# SCH_pcie_2022-12-23.net
KiCad netlist of a schematic drawn in EasyEDA
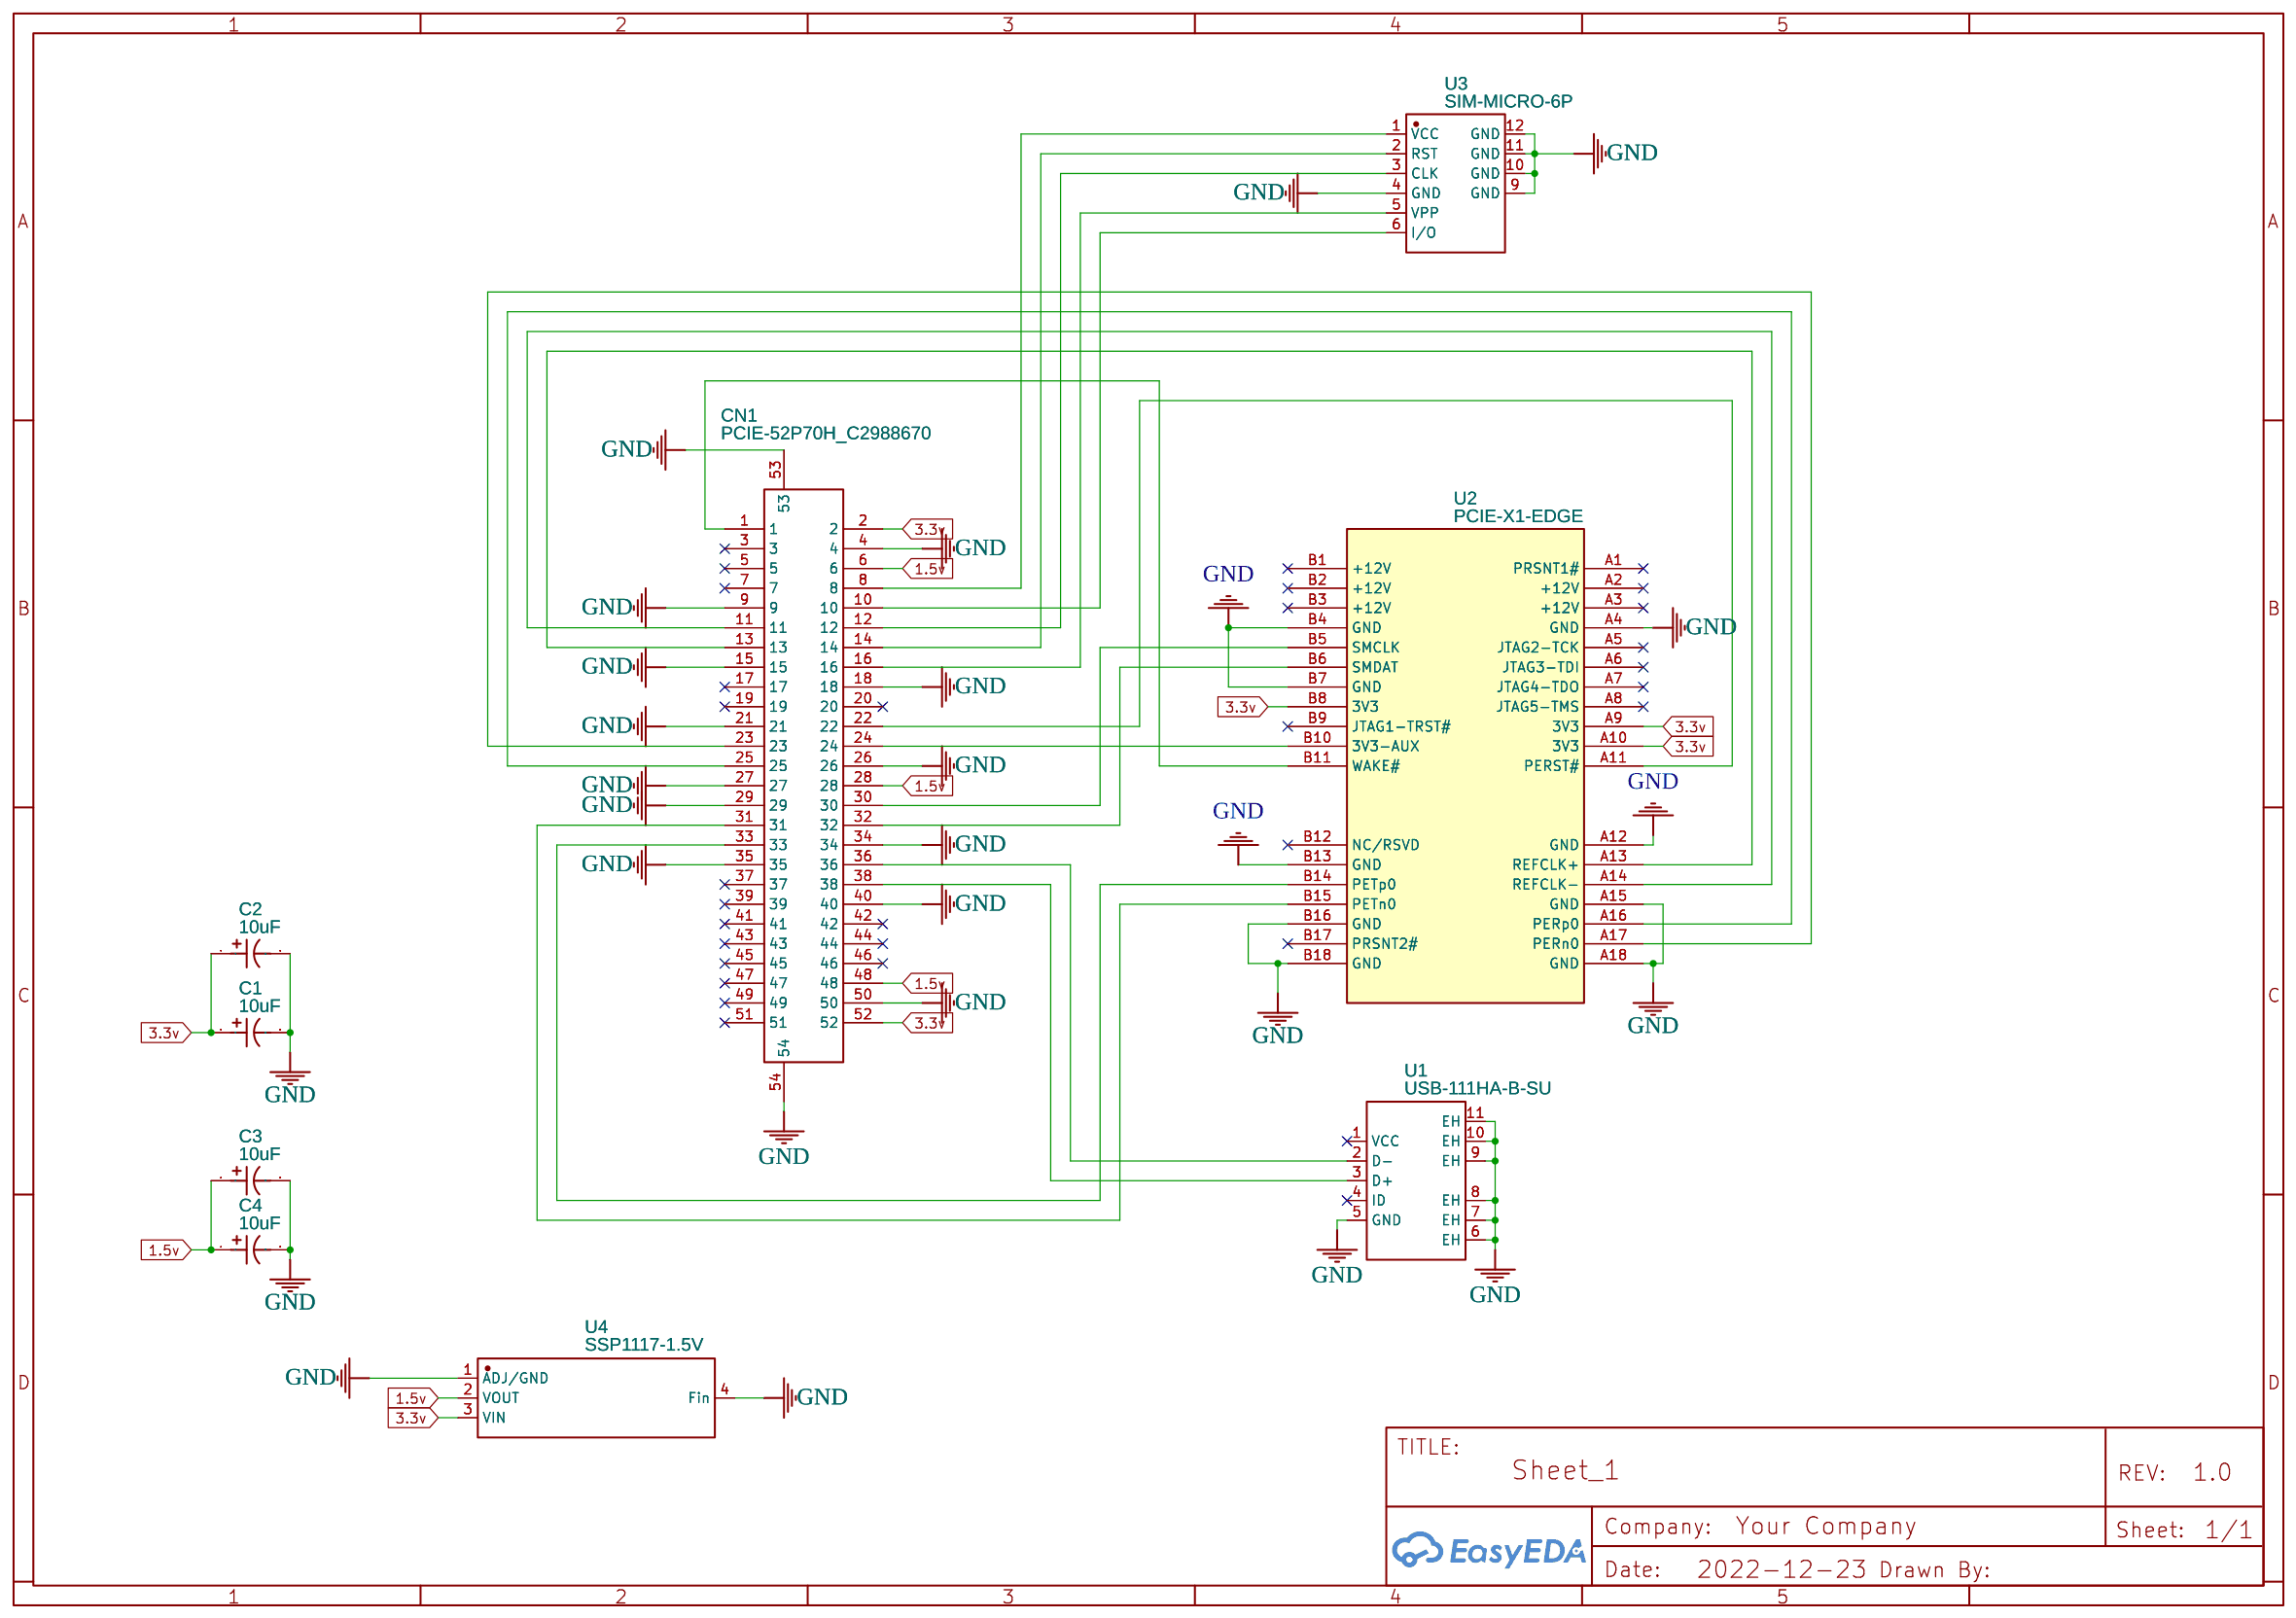
[diagram p0: schematic sheet]

(export (version "E")
  (design (tool "Eeschema 10.0.6"))
  (components
    (comp (ref "C1")
      (value "10uF")
      (fields
        (field (name "BOM_Manufacturer Part") "XT10UF35V90RV0070")
        (field (name "BOM_Supplier Part") "C2992602")
      )
      (libsource (lib "") (part "XT10UF35V90RV0070_1"))
    )
    (comp (ref "C2")
      (value "10uF")
      (fields
        (field (name "BOM_Manufacturer Part") "XT10UF35V90RV0070")
        (field (name "BOM_Supplier Part") "C2992602")
      )
      (libsource (lib "") (part "XT10UF35V90RV0070_1"))
    )
    (comp (ref "C3")
      (value "10uF")
      (fields
        (field (name "BOM_Manufacturer Part") "XT10UF35V90RV0070")
        (field (name "BOM_Supplier Part") "C2992602")
      )
      (libsource (lib "") (part "XT10UF35V90RV0070"))
    )
    (comp (ref "C4")
      (value "10uF")
      (fields
        (field (name "BOM_Manufacturer Part") "XT10UF35V90RV0070")
        (field (name "BOM_Supplier Part") "C2992602")
      )
      (libsource (lib "") (part "XT10UF35V90RV0070"))
    )
    (comp (ref "CN1")
      (value "PCIE-52P70H_C2988670")
      (fields
        (field (name "BOM_Manufacturer Part") "PCIE-52P70H")
        (field (name "BOM_Supplier Part") "C2988670")
      )
      (libsource (lib "") (part "PCIE-52P70H_C2988670"))
    )
    (comp (ref "U1")
      (value "USB-111HA-B-SU")
      (fields (field (name "BOM_Supplier Part") "C2939565"))
      (libsource (lib "") (part "USB-111HA-B-SU"))
    )
    (comp (ref "U2") (value "PCIE-X1-EDGE") (libsource (lib "") (part "PCIE-X1-EDGE")))
    (comp (ref "U3")
      (value "SIM-MICRO-6P")
      (fields (field (name "BOM_Supplier Part") "C9900009166"))
      (libsource (lib "") (part "SIM-MICRO-6P"))
    )
    (comp (ref "U4")
      (value "SSP1117-1.5V")
      (fields (field (name "BOM_Supplier Part") "C308941"))
      (libsource (lib "") (part "SSP1117-1.5V"))
    )
  )
  (nets
    (net (code "1") (name "1.5v") (class "Default")
      (node (ref "C3") (pin "1") (pinfunction "1_1") (pintype "input"))
      (node (ref "C4") (pin "1") (pinfunction "1_1") (pintype "input"))
      (node (ref "CN1") (pin "28") (pinfunction "28_28") (pintype "unspecified"))
      (node (ref "CN1") (pin "48") (pinfunction "48_48") (pintype "unspecified"))
      (node (ref "CN1") (pin "6") (pinfunction "6_6") (pintype "unspecified"))
      (node (ref "U4") (pin "2") (pinfunction "VOUT_2") (pintype "unspecified"))
    )
    (net (code "2") (name "3.3v") (class "Default")
      (node (ref "C1") (pin "1") (pinfunction "1_1") (pintype "input"))
      (node (ref "C2") (pin "1") (pinfunction "1_1") (pintype "input"))
      (node (ref "CN1") (pin "2") (pinfunction "2_2") (pintype "unspecified"))
      (node (ref "CN1") (pin "52") (pinfunction "52_52") (pintype "unspecified"))
      (node (ref "U2") (pin "A10") (pinfunction "3V3_A10") (pintype "unspecified"))
      (node (ref "U2") (pin "A9") (pinfunction "3V3_A9") (pintype "unspecified"))
      (node (ref "U2") (pin "B8") (pinfunction "3V3_B8") (pintype "unspecified"))
      (node (ref "U4") (pin "3") (pinfunction "VIN_3") (pintype "unspecified"))
    )
    (net (code "3") (name "GND") (class "Default")
      (node (ref "C1") (pin "2") (pinfunction "2_2") (pintype "input"))
      (node (ref "C2") (pin "2") (pinfunction "2_2") (pintype "input"))
      (node (ref "C3") (pin "2") (pinfunction "2_2") (pintype "input"))
      (node (ref "C4") (pin "2") (pinfunction "2_2") (pintype "input"))
      (node (ref "CN1") (pin "15") (pinfunction "15_15") (pintype "unspecified"))
      (node (ref "CN1") (pin "18") (pinfunction "18_18") (pintype "unspecified"))
      (node (ref "CN1") (pin "21") (pinfunction "21_21") (pintype "unspecified"))
      (node (ref "CN1") (pin "26") (pinfunction "26_26") (pintype "unspecified"))
      (node (ref "CN1") (pin "27") (pinfunction "27_27") (pintype "unspecified"))
      (node (ref "CN1") (pin "29") (pinfunction "29_29") (pintype "unspecified"))
      (node (ref "CN1") (pin "34") (pinfunction "34_34") (pintype "unspecified"))
      (node (ref "CN1") (pin "35") (pinfunction "35_35") (pintype "unspecified"))
      (node (ref "CN1") (pin "4") (pinfunction "4_4") (pintype "unspecified"))
      (node (ref "CN1") (pin "40") (pinfunction "40_40") (pintype "unspecified"))
      (node (ref "CN1") (pin "50") (pinfunction "50_50") (pintype "unspecified"))
      (node (ref "CN1") (pin "53") (pinfunction "53_53") (pintype "unspecified"))
      (node (ref "CN1") (pin "54") (pinfunction "54_54") (pintype "unspecified"))
      (node (ref "CN1") (pin "9") (pinfunction "9_9") (pintype "unspecified"))
      (node (ref "U1") (pin "10") (pinfunction "EH_10") (pintype "unspecified"))
      (node (ref "U1") (pin "11") (pinfunction "EH_11") (pintype "unspecified"))
      (node (ref "U1") (pin "5") (pinfunction "GND_5") (pintype "input"))
      (node (ref "U1") (pin "6") (pinfunction "EH_6") (pintype "unspecified"))
      (node (ref "U1") (pin "7") (pinfunction "EH_7") (pintype "unspecified"))
      (node (ref "U1") (pin "8") (pinfunction "EH_8") (pintype "unspecified"))
      (node (ref "U1") (pin "9") (pinfunction "EH_9") (pintype "unspecified"))
      (node (ref "U2") (pin "A12") (pinfunction "GND_A12") (pintype "unspecified"))
      (node (ref "U2") (pin "A15") (pinfunction "GND_A15") (pintype "unspecified"))
      (node (ref "U2") (pin "A18") (pinfunction "GND_A18") (pintype "unspecified"))
      (node (ref "U2") (pin "A4") (pinfunction "GND_A4") (pintype "unspecified"))
      (node (ref "U2") (pin "B13") (pinfunction "GND_B13") (pintype "unspecified"))
      (node (ref "U2") (pin "B16") (pinfunction "GND_B16") (pintype "unspecified"))
      (node (ref "U2") (pin "B18") (pinfunction "GND_B18") (pintype "unspecified"))
      (node (ref "U2") (pin "B4") (pinfunction "GND_B4") (pintype "unspecified"))
      (node (ref "U2") (pin "B7") (pinfunction "GND_B7") (pintype "unspecified"))
      (node (ref "U3") (pin "10") (pinfunction "GND_10") (pintype "unspecified"))
      (node (ref "U3") (pin "11") (pinfunction "GND_11") (pintype "unspecified"))
      (node (ref "U3") (pin "12") (pinfunction "GND_12") (pintype "unspecified"))
      (node (ref "U3") (pin "4") (pinfunction "GND_4") (pintype "unspecified"))
      (node (ref "U3") (pin "9") (pinfunction "GND_9") (pintype "unspecified"))
      (node (ref "U4") (pin "1") (pinfunction "ADJ/GND_1") (pintype "unspecified"))
      (node (ref "U4") (pin "4") (pinfunction "Fin_4") (pintype "unspecified"))
    )
    (net (code "4") (name "Net-(U1-D+)") (class "Default")
      (node (ref "CN1") (pin "38") (pinfunction "38_38") (pintype "unspecified"))
      (node (ref "U1") (pin "3") (pinfunction "D+_3") (pintype "input"))
    )
    (net (code "5") (name "Net-(U1-D-)") (class "Default")
      (node (ref "CN1") (pin "36") (pinfunction "36_36") (pintype "unspecified"))
      (node (ref "U1") (pin "2") (pinfunction "D-_2") (pintype "input"))
    )
    (net (code "6") (name "Net-(U2-3V3-AUX)") (class "Default")
      (node (ref "CN1") (pin "24") (pinfunction "24_24") (pintype "unspecified"))
      (node (ref "U2") (pin "B10") (pinfunction "3V3-AUX_B10") (pintype "unspecified"))
    )
    (net (code "7") (name "Net-(U2-PERST#)") (class "Default")
      (node (ref "CN1") (pin "22") (pinfunction "22_22") (pintype "unspecified"))
      (node (ref "U2") (pin "A11") (pinfunction "PERST#_A11") (pintype "unspecified"))
    )
    (net (code "8") (name "Net-(U2-PERn0)") (class "Default")
      (node (ref "CN1") (pin "23") (pinfunction "23_23") (pintype "unspecified"))
      (node (ref "U2") (pin "A17") (pinfunction "PERn0_A17") (pintype "unspecified"))
    )
    (net (code "9") (name "Net-(U2-PERp0)") (class "Default")
      (node (ref "CN1") (pin "25") (pinfunction "25_25") (pintype "unspecified"))
      (node (ref "U2") (pin "A16") (pinfunction "PERp0_A16") (pintype "unspecified"))
    )
    (net (code "10") (name "Net-(U2-PETn0)") (class "Default")
      (node (ref "CN1") (pin "31") (pinfunction "31_31") (pintype "unspecified"))
      (node (ref "U2") (pin "B15") (pinfunction "PETn0_B15") (pintype "unspecified"))
    )
    (net (code "11") (name "Net-(U2-PETp0)") (class "Default")
      (node (ref "CN1") (pin "33") (pinfunction "33_33") (pintype "unspecified"))
      (node (ref "U2") (pin "B14") (pinfunction "PETp0_B14") (pintype "unspecified"))
    )
    (net (code "12") (name "Net-(U2-REFCLK+)") (class "Default")
      (node (ref "CN1") (pin "13") (pinfunction "13_13") (pintype "unspecified"))
      (node (ref "U2") (pin "A13") (pinfunction "REFCLK+_A13") (pintype "unspecified"))
    )
    (net (code "13") (name "Net-(U2-REFCLK-)") (class "Default")
      (node (ref "CN1") (pin "11") (pinfunction "11_11") (pintype "unspecified"))
      (node (ref "U2") (pin "A14") (pinfunction "REFCLK-_A14") (pintype "unspecified"))
    )
    (net (code "14") (name "Net-(U2-SMCLK)") (class "Default")
      (node (ref "CN1") (pin "30") (pinfunction "30_30") (pintype "unspecified"))
      (node (ref "U2") (pin "B5") (pinfunction "SMCLK_B5") (pintype "unspecified"))
    )
    (net (code "15") (name "Net-(U2-SMDAT)") (class "Default")
      (node (ref "CN1") (pin "32") (pinfunction "32_32") (pintype "unspecified"))
      (node (ref "U2") (pin "B6") (pinfunction "SMDAT_B6") (pintype "unspecified"))
    )
    (net (code "16") (name "Net-(U2-WAKE#)") (class "Default")
      (node (ref "CN1") (pin "1") (pinfunction "1_1") (pintype "unspecified"))
      (node (ref "U2") (pin "B11") (pinfunction "WAKE#_B11") (pintype "unspecified"))
    )
    (net (code "17") (name "Net-(U3-CLK)") (class "Default")
      (node (ref "CN1") (pin "12") (pinfunction "12_12") (pintype "unspecified"))
      (node (ref "U3") (pin "3") (pinfunction "CLK_3") (pintype "unspecified"))
    )
    (net (code "18") (name "Net-(U3-I{slash}O)") (class "Default")
      (node (ref "CN1") (pin "10") (pinfunction "10_10") (pintype "unspecified"))
      (node (ref "U3") (pin "6") (pinfunction "I/O_6") (pintype "unspecified"))
    )
    (net (code "19") (name "Net-(U3-RST)") (class "Default")
      (node (ref "CN1") (pin "14") (pinfunction "14_14") (pintype "unspecified"))
      (node (ref "U3") (pin "2") (pinfunction "RST_2") (pintype "unspecified"))
    )
    (net (code "20") (name "Net-(U3-VCC)") (class "Default")
      (node (ref "CN1") (pin "8") (pinfunction "8_8") (pintype "unspecified"))
      (node (ref "U3") (pin "1") (pinfunction "VCC_1") (pintype "unspecified"))
    )
    (net (code "21") (name "Net-(U3-VPP)") (class "Default")
      (node (ref "CN1") (pin "16") (pinfunction "16_16") (pintype "unspecified"))
      (node (ref "U3") (pin "5") (pinfunction "VPP_5") (pintype "unspecified"))
    )
    (net (code "22") (name "unconnected-(CN1-Pad3)") (class "Default")
      (node (ref "CN1") (pin "3") (pinfunction "3_3") (pintype "unspecified+no_connect"))
    )
    (net (code "23") (name "unconnected-(CN1-Pad5)") (class "Default")
      (node (ref "CN1") (pin "5") (pinfunction "5_5") (pintype "unspecified+no_connect"))
    )
    (net (code "24") (name "unconnected-(CN1-Pad7)") (class "Default")
      (node (ref "CN1") (pin "7") (pinfunction "7_7") (pintype "unspecified+no_connect"))
    )
    (net (code "25") (name "unconnected-(CN1-Pad17)") (class "Default")
      (node (ref "CN1") (pin "17") (pinfunction "17_17") (pintype "unspecified+no_connect"))
    )
    (net (code "26") (name "unconnected-(CN1-Pad19)") (class "Default")
      (node (ref "CN1") (pin "19") (pinfunction "19_19") (pintype "unspecified+no_connect"))
    )
    (net (code "27") (name "unconnected-(CN1-Pad20)") (class "Default")
      (node (ref "CN1") (pin "20") (pinfunction "20_20") (pintype "unspecified+no_connect"))
    )
    (net (code "28") (name "unconnected-(CN1-Pad37)") (class "Default")
      (node (ref "CN1") (pin "37") (pinfunction "37_37") (pintype "unspecified+no_connect"))
    )
    (net (code "29") (name "unconnected-(CN1-Pad39)") (class "Default")
      (node (ref "CN1") (pin "39") (pinfunction "39_39") (pintype "unspecified+no_connect"))
    )
    (net (code "30") (name "unconnected-(CN1-Pad41)") (class "Default")
      (node (ref "CN1") (pin "41") (pinfunction "41_41") (pintype "unspecified+no_connect"))
    )
    (net (code "31") (name "unconnected-(CN1-Pad42)") (class "Default")
      (node (ref "CN1") (pin "42") (pinfunction "42_42") (pintype "unspecified+no_connect"))
    )
    (net (code "32") (name "unconnected-(CN1-Pad43)") (class "Default")
      (node (ref "CN1") (pin "43") (pinfunction "43_43") (pintype "unspecified+no_connect"))
    )
    (net (code "33") (name "unconnected-(CN1-Pad44)") (class "Default")
      (node (ref "CN1") (pin "44") (pinfunction "44_44") (pintype "unspecified+no_connect"))
    )
    (net (code "34") (name "unconnected-(CN1-Pad45)") (class "Default")
      (node (ref "CN1") (pin "45") (pinfunction "45_45") (pintype "unspecified+no_connect"))
    )
    (net (code "35") (name "unconnected-(CN1-Pad46)") (class "Default")
      (node (ref "CN1") (pin "46") (pinfunction "46_46") (pintype "unspecified+no_connect"))
    )
    (net (code "36") (name "unconnected-(CN1-Pad47)") (class "Default")
      (node (ref "CN1") (pin "47") (pinfunction "47_47") (pintype "unspecified+no_connect"))
    )
    (net (code "37") (name "unconnected-(CN1-Pad49)") (class "Default")
      (node (ref "CN1") (pin "49") (pinfunction "49_49") (pintype "unspecified+no_connect"))
    )
    (net (code "38") (name "unconnected-(CN1-Pad51)") (class "Default")
      (node (ref "CN1") (pin "51") (pinfunction "51_51") (pintype "unspecified+no_connect"))
    )
    (net (code "39") (name "unconnected-(U1-ID-Pad4)") (class "Default")
      (node (ref "U1") (pin "4") (pinfunction "ID_4") (pintype "input+no_connect"))
    )
    (net (code "40") (name "unconnected-(U1-VCC-Pad1)") (class "Default")
      (node (ref "U1") (pin "1") (pinfunction "VCC_1") (pintype "input+no_connect"))
    )
    (net (code "41") (name "unconnected-(U2-+12V-PadA2)") (class "Default")
      (node (ref "U2") (pin "A2") (pinfunction "+12V_A2") (pintype "unspecified+no_connect"))
    )
    (net (code "42") (name "unconnected-(U2-+12V-PadA3)") (class "Default")
      (node (ref "U2") (pin "A3") (pinfunction "+12V_A3") (pintype "unspecified+no_connect"))
    )
    (net (code "43") (name "unconnected-(U2-+12V-PadB1)") (class "Default")
      (node (ref "U2") (pin "B1") (pinfunction "+12V_B1") (pintype "unspecified+no_connect"))
    )
    (net (code "44") (name "unconnected-(U2-+12V-PadB2)") (class "Default")
      (node (ref "U2") (pin "B2") (pinfunction "+12V_B2") (pintype "unspecified+no_connect"))
    )
    (net (code "45") (name "unconnected-(U2-+12V-PadB3)") (class "Default")
      (node (ref "U2") (pin "B3") (pinfunction "+12V_B3") (pintype "unspecified+no_connect"))
    )
    (net (code "46") (name "unconnected-(U2-JTAG1-TRST#-PadB9)") (class "Default")
      (node (ref "U2") (pin "B9") (pinfunction "JTAG1-TRST#_B9") (pintype "unspecified+no_connect"))
    )
    (net (code "47") (name "unconnected-(U2-JTAG2-TCK-PadA5)") (class "Default")
      (node (ref "U2") (pin "A5") (pinfunction "JTAG2-TCK_A5") (pintype "unspecified+no_connect"))
    )
    (net (code "48") (name "unconnected-(U2-JTAG3-TDI-PadA6)") (class "Default")
      (node (ref "U2") (pin "A6") (pinfunction "JTAG3-TDI_A6") (pintype "unspecified+no_connect"))
    )
    (net (code "49") (name "unconnected-(U2-JTAG4-TDO-PadA7)") (class "Default")
      (node (ref "U2") (pin "A7") (pinfunction "JTAG4-TDO_A7") (pintype "unspecified+no_connect"))
    )
    (net (code "50") (name "unconnected-(U2-JTAG5-TMS-PadA8)") (class "Default")
      (node (ref "U2") (pin "A8") (pinfunction "JTAG5-TMS_A8") (pintype "unspecified+no_connect"))
    )
    (net (code "51") (name "unconnected-(U2-NC{slash}RSVD-PadB12)") (class "Default")
      (node (ref "U2") (pin "B12") (pinfunction "NC/RSVD_B12") (pintype "unspecified+no_connect"))
    )
    (net (code "52") (name "unconnected-(U2-PRSNT1#-PadA1)") (class "Default")
      (node (ref "U2") (pin "A1") (pinfunction "PRSNT1#_A1") (pintype "unspecified+no_connect"))
    )
    (net (code "53") (name "unconnected-(U2-PRSNT2#-PadB17)") (class "Default")
      (node (ref "U2") (pin "B17") (pinfunction "PRSNT2#_B17") (pintype "unspecified+no_connect"))
    )
  )
)
